# puissance.net
KiCad netlist of a schematic drawn in Altium Designer
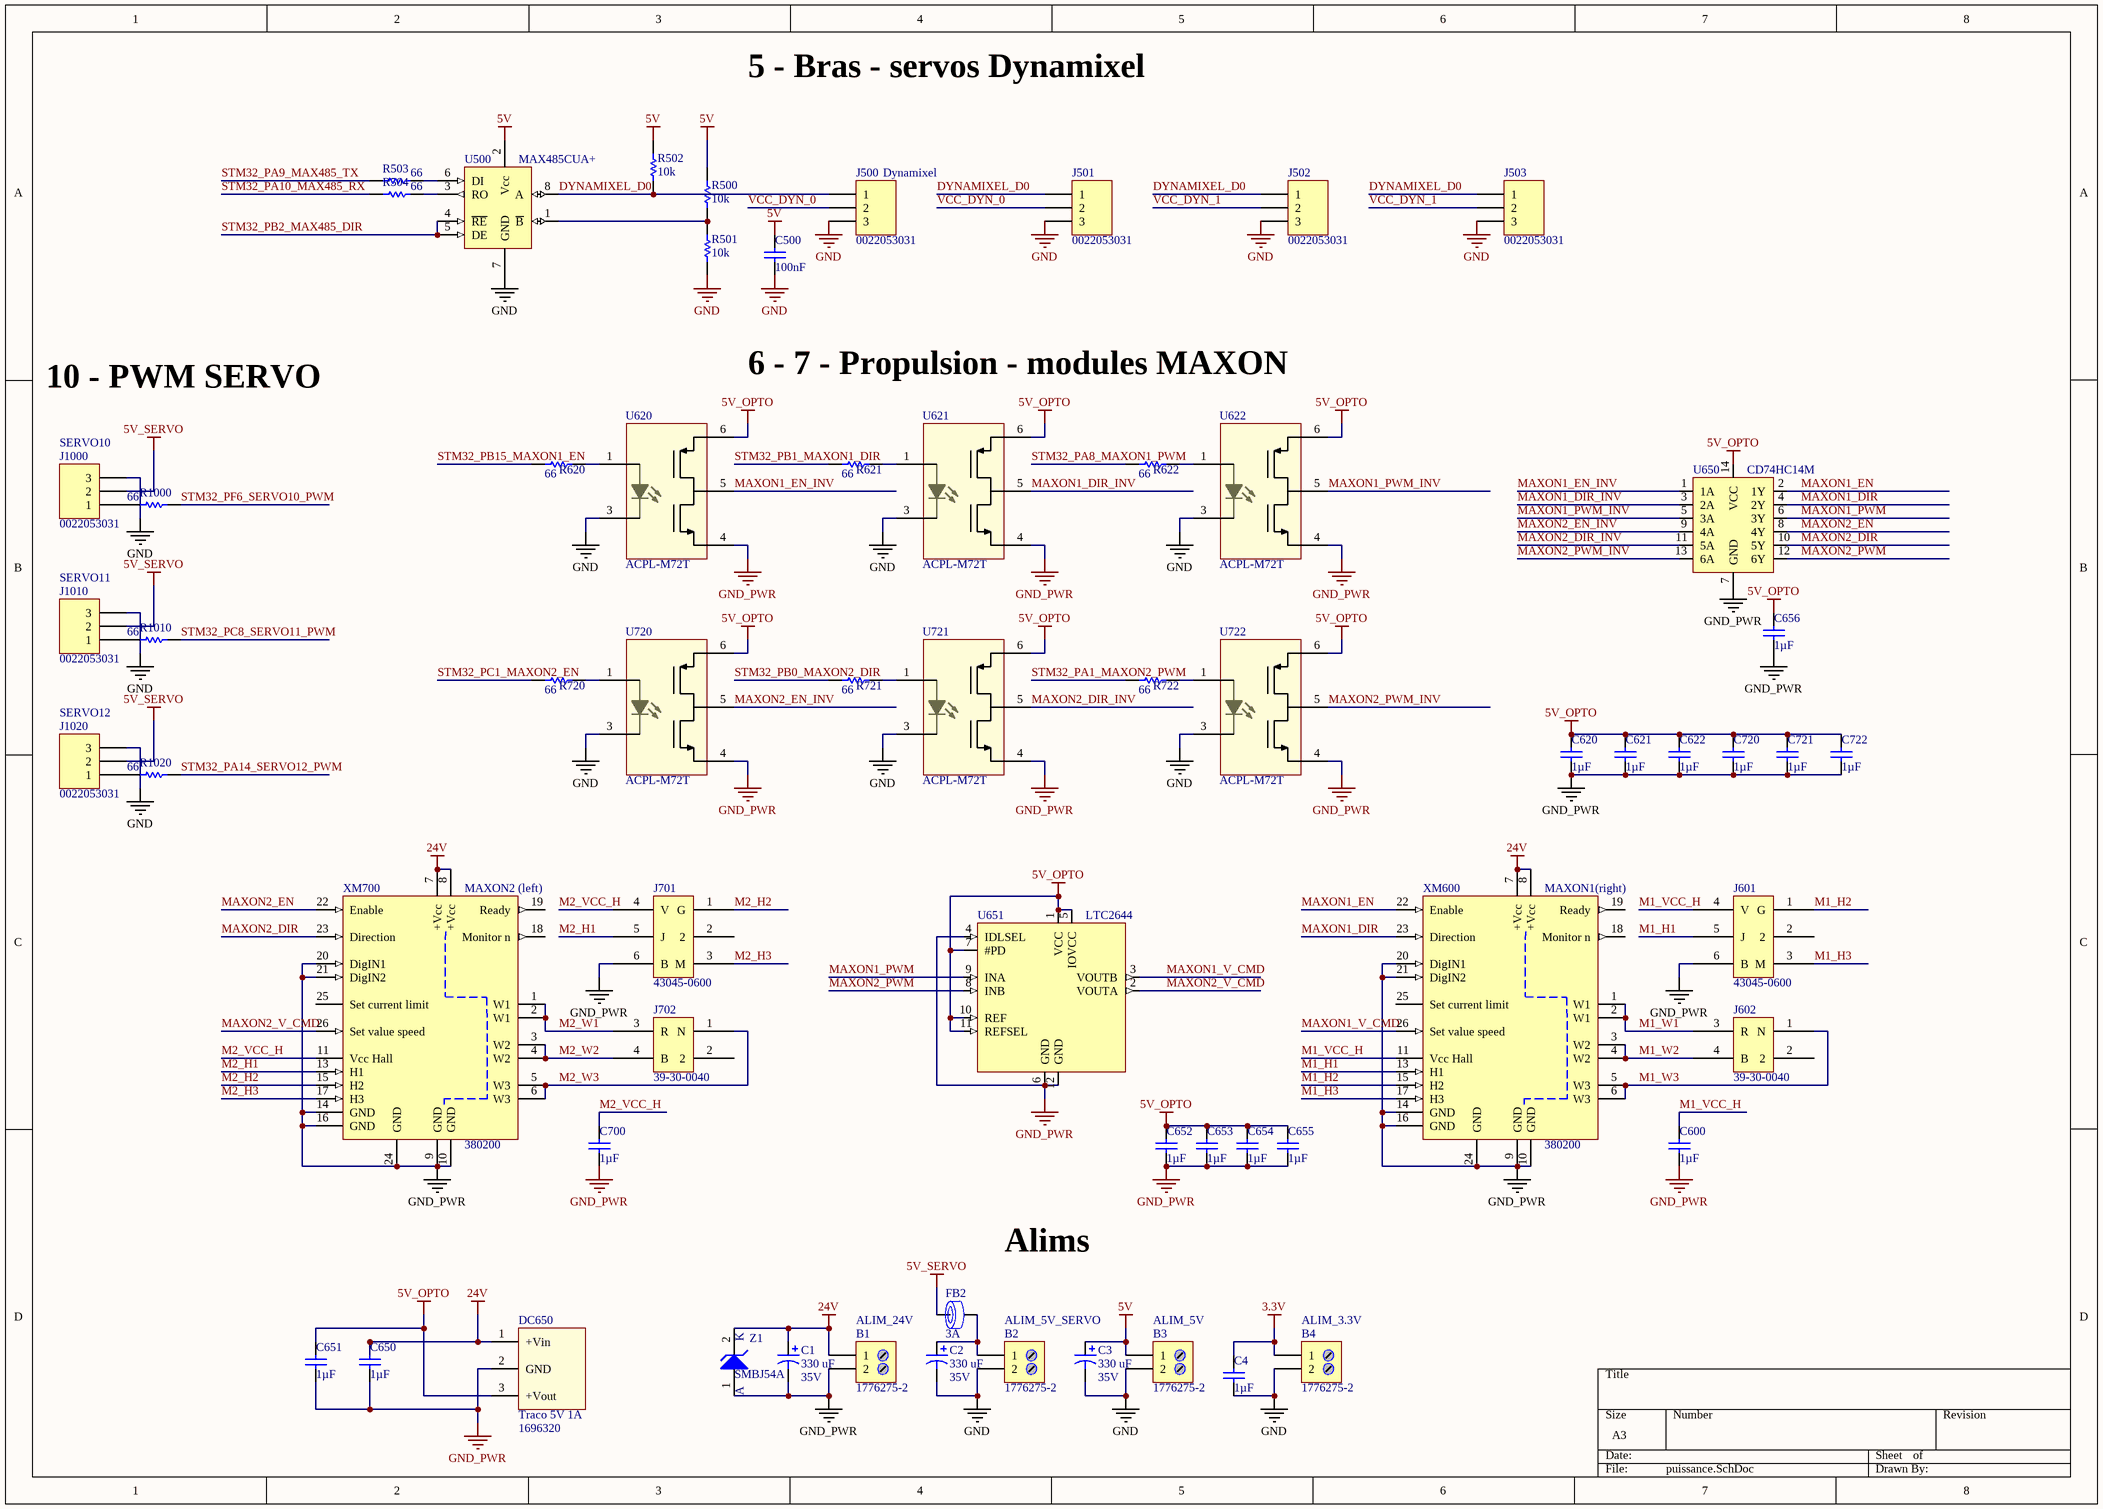
[diagram p0: puissance.SchDoc]

(export (version "E")
  (design (tool "Eeschema 10.0.6"))
  (components
    (comp (ref "B1")
      (value "1776275-2")
      (footprint "BORNIER_2V_3.5MM")
      (description "TERM BLOCK 2POS SIDE ENT 3.5MM")
      (fields (field (name "MANUFACTURER") "TE Connectivity AMP Connectors"))
      (libsource (lib "Divers") (part "1776275-2"))
    )
    (comp (ref "B2")
      (value "1776275-2")
      (footprint "BORNIER_2V_3.5MM")
      (description "TERM BLOCK 2POS SIDE ENT 3.5MM")
      (fields (field (name "MANUFACTURER") "TE Connectivity AMP Connectors"))
      (libsource (lib "Divers") (part "1776275-2"))
    )
    (comp (ref "B3")
      (value "1776275-2")
      (footprint "BORNIER_2V_3.5MM")
      (description "TERM BLOCK 2POS SIDE ENT 3.5MM")
      (fields (field (name "MANUFACTURER") "TE Connectivity AMP Connectors"))
      (libsource (lib "Divers") (part "1776275-2"))
    )
    (comp (ref "B4")
      (value "1776275-2")
      (footprint "BORNIER_2V_3.5MM")
      (description "TERM BLOCK 2POS SIDE ENT 3.5MM")
      (fields (field (name "MANUFACTURER") "TE Connectivity AMP Connectors"))
      (libsource (lib "Divers") (part "1776275-2"))
    )
    (comp (ref "C1")
      (value "330 uF")
      (footprint "WCAP-ATG8_10x12.5x5x0.6")
      (description "CAP Alu 330 UF 20% 35 V")
      (fields
        (field (name "MANUFACTURER") "Wurth Elektronik")
        (field (name "MANUFACTURER PART NUMBER") "860010575012")
        (field (name "RATEDVOLTAGE") "35V")
      )
      (libsource (lib "Condensateur") (part "WCAP-ATG8, 860010575012"))
    )
    (comp (ref "C2")
      (value "330 uF")
      (footprint "WCAP-ATG8_10x12.5x5x0.6")
      (description "CAP Alu 330 UF 20% 35 V")
      (fields
        (field (name "MANUFACTURER") "Wurth Elektronik")
        (field (name "MANUFACTURER PART NUMBER") "860010575012")
        (field (name "RATEDVOLTAGE") "35V")
      )
      (libsource (lib "Condensateur") (part "WCAP-ATG8, 860010575012"))
    )
    (comp (ref "C3")
      (value "330 uF")
      (footprint "WCAP-ATG8_10x12.5x5x0.6")
      (description "CAP Alu 330 UF 20% 35 V")
      (fields
        (field (name "MANUFACTURER") "Wurth Elektronik")
        (field (name "MANUFACTURER PART NUMBER") "860010575012")
        (field (name "RATEDVOLTAGE") "35V")
      )
      (libsource (lib "Condensateur") (part "WCAP-ATG8, 860010575012"))
    )
    (comp (ref "C4")
      (value "1µF")
      (footprint "C0805_N")
      (description "Capacitor")
      (fields (field (name "PUBLISHER") "Altium Limited"))
      (libsource (lib "_ROBOT") (part "Condensateur"))
    )
    (comp (ref "C500")
      (value "100nF")
      (footprint "C0805_N")
      (description "Capacitor")
      (fields (field (name "PUBLISHER") "Altium Limited"))
      (libsource (lib "_ROBOT") (part "Condensateur"))
    )
    (comp (ref "C600")
      (value "1µF")
      (footprint "C0805_N")
      (description "Capacitor")
      (fields (field (name "PUBLISHER") "Altium Limited"))
      (libsource (lib "_ROBOT") (part "Condensateur"))
    )
    (comp (ref "C620")
      (value "1µF")
      (footprint "C0805_N")
      (description "Capacitor")
      (fields (field (name "PUBLISHER") "Altium Limited"))
      (libsource (lib "_ROBOT") (part "Condensateur"))
    )
    (comp (ref "C621")
      (value "1µF")
      (footprint "C0805_N")
      (description "Capacitor")
      (fields (field (name "PUBLISHER") "Altium Limited"))
      (libsource (lib "_ROBOT") (part "Condensateur"))
    )
    (comp (ref "C622")
      (value "1µF")
      (footprint "C0805_N")
      (description "Capacitor")
      (fields (field (name "PUBLISHER") "Altium Limited"))
      (libsource (lib "_ROBOT") (part "Condensateur"))
    )
    (comp (ref "C650")
      (value "1µF")
      (footprint "C0805_N")
      (description "Capacitor")
      (fields (field (name "PUBLISHER") "Altium Limited"))
      (libsource (lib "_ROBOT") (part "Condensateur"))
    )
    (comp (ref "C651")
      (value "1µF")
      (footprint "C0805_N")
      (description "Capacitor")
      (fields (field (name "PUBLISHER") "Altium Limited"))
      (libsource (lib "_ROBOT") (part "Condensateur"))
    )
    (comp (ref "C652")
      (value "1µF")
      (footprint "C0805_N")
      (description "Capacitor")
      (fields (field (name "PUBLISHER") "Altium Limited"))
      (libsource (lib "_ROBOT") (part "Condensateur"))
    )
    (comp (ref "C653")
      (value "1µF")
      (footprint "C0805_N")
      (description "Capacitor")
      (fields (field (name "PUBLISHER") "Altium Limited"))
      (libsource (lib "_ROBOT") (part "Condensateur"))
    )
    (comp (ref "C654")
      (value "1µF")
      (footprint "C0805_N")
      (description "Capacitor")
      (fields (field (name "PUBLISHER") "Altium Limited"))
      (libsource (lib "_ROBOT") (part "Condensateur"))
    )
    (comp (ref "C655")
      (value "1µF")
      (footprint "C0805_N")
      (description "Capacitor")
      (fields (field (name "PUBLISHER") "Altium Limited"))
      (libsource (lib "_ROBOT") (part "Condensateur"))
    )
    (comp (ref "C656")
      (value "1µF")
      (footprint "C0805_N")
      (description "Capacitor")
      (fields (field (name "PUBLISHER") "Altium Limited"))
      (libsource (lib "_ROBOT") (part "Condensateur"))
    )
    (comp (ref "C700")
      (value "1µF")
      (footprint "C0805_N")
      (description "Capacitor")
      (fields (field (name "PUBLISHER") "Altium Limited"))
      (libsource (lib "_ROBOT") (part "Condensateur"))
    )
    (comp (ref "C720")
      (value "1µF")
      (footprint "C0805_N")
      (description "Capacitor")
      (fields (field (name "PUBLISHER") "Altium Limited"))
      (libsource (lib "_ROBOT") (part "Condensateur"))
    )
    (comp (ref "C721")
      (value "1µF")
      (footprint "C0805_N")
      (description "Capacitor")
      (fields (field (name "PUBLISHER") "Altium Limited"))
      (libsource (lib "_ROBOT") (part "Condensateur"))
    )
    (comp (ref "C722")
      (value "1µF")
      (footprint "C0805_N")
      (description "Capacitor")
      (fields (field (name "PUBLISHER") "Altium Limited"))
      (libsource (lib "_ROBOT") (part "Condensateur"))
    )
    (comp (ref "DC650")
      (value "Traco 5V 1A")
      (footprint "TSR1")
      (description "Traco 12.0V 12W 1A")
      (fields
        (field (name "MANUFACTURER") "TRACOPOWER")
        (field (name "MANUFACTURER PART NUMBER") "TSR1-2450")
        (field (name "SUPPLIER PART NUMBER 1") "1696320")
      )
      (libsource (lib "Alimentation") (part "TSR1-24120"))
    )
    (comp (ref "FB2")
      (value "742792023")
      (footprint "WE-CBF_0805_High Current")
      (description "Ferrite Bead 120ohm 0805 max3.0A")
      (fields (field (name "MANUFACTURER") "Wurth Elektronik") (field (name "RATEDCURRENT") "3A"))
      (libsource (lib "Inductance") (part "WE-CBF, 742792023"))
    )
    (comp (ref "J500")
      (value "0022053031")
      (footprint "HDR1X3")
      (description "CONN HEADER 3POS .100 R/A TIN")
      (fields (field (name "MANUFACTURER") "Molex, LLC"))
      (libsource (lib "Divers") (part "0022053031"))
    )
    (comp (ref "J501")
      (value "0022053031")
      (footprint "HDR1X3")
      (description "CONN HEADER 3POS .100 R/A TIN")
      (fields (field (name "MANUFACTURER") "Molex, LLC"))
      (libsource (lib "Divers") (part "0022053031"))
    )
    (comp (ref "J502")
      (value "0022053031")
      (footprint "HDR1X3")
      (description "CONN HEADER 3POS .100 R/A TIN")
      (fields (field (name "MANUFACTURER") "Molex, LLC"))
      (libsource (lib "Divers") (part "0022053031"))
    )
    (comp (ref "J503")
      (value "0022053031")
      (footprint "HDR1X3")
      (description "CONN HEADER 3POS .100 R/A TIN")
      (fields (field (name "MANUFACTURER") "Molex, LLC"))
      (libsource (lib "Divers") (part "0022053031"))
    )
    (comp (ref "J601")
      (value "43045-0600")
      (footprint "Molex:43045-0600")
      (description "CONN HEADER 6POS 3MM RT ANG TIN")
      (fields (field (name "MANUFACTURER") "MOLEX"))
      (libsource (lib "Connecteurs") (part "43045-0600"))
    )
    (comp (ref "J602")
      (value "39-30-0040")
      (footprint "Molex:39-30-0040")
      (description "MOLEX  39-30-0040 4.2 mm, 4 Contact(s)")
      (fields (field (name "MANUFACTURER") "MOLEX"))
      (libsource (lib "Connecteurs") (part "39-30-0040"))
    )
    (comp (ref "J701")
      (value "43045-0600")
      (footprint "Molex:43045-0600")
      (description "CONN HEADER 6POS 3MM RT ANG TIN")
      (fields (field (name "MANUFACTURER") "MOLEX"))
      (libsource (lib "Connecteurs") (part "43045-0600"))
    )
    (comp (ref "J702")
      (value "39-30-0040")
      (footprint "Molex:39-30-0040")
      (description "MOLEX  39-30-0040 4.2 mm, 4 Contact(s)")
      (fields (field (name "MANUFACTURER") "MOLEX"))
      (libsource (lib "Connecteurs") (part "39-30-0040"))
    )
    (comp (ref "J1000")
      (value "0022053031")
      (footprint "HDR1X3")
      (description "CONN HEADER 3POS .100 R/A TIN")
      (fields (field (name "MANUFACTURER") "Molex, LLC"))
      (libsource (lib "") (part "0022053031_1"))
    )
    (comp (ref "J1010")
      (value "0022053031")
      (footprint "HDR1X3")
      (description "CONN HEADER 3POS .100 R/A TIN")
      (fields (field (name "MANUFACTURER") "Molex, LLC"))
      (libsource (lib "") (part "0022053031_1"))
    )
    (comp (ref "J1020")
      (value "0022053031")
      (footprint "HDR1X3")
      (description "CONN HEADER 3POS .100 R/A TIN")
      (fields (field (name "MANUFACTURER") "Molex, LLC"))
      (libsource (lib "") (part "0022053031_1"))
    )
    (comp (ref "R500")
      (value "10k")
      (footprint "R0805_N")
      (description "Resistor")
      (fields (field (name "PUBLISHER") "Altium Limited"))
      (libsource (lib "_ROBOT") (part "Resistor"))
    )
    (comp (ref "R501")
      (value "10k")
      (footprint "R0805_N")
      (description "Resistor")
      (fields (field (name "PUBLISHER") "Altium Limited"))
      (libsource (lib "_ROBOT") (part "Resistor"))
    )
    (comp (ref "R502")
      (value "10k")
      (footprint "R0805_N")
      (description "Resistor")
      (fields (field (name "PUBLISHER") "Altium Limited"))
      (libsource (lib "_ROBOT") (part "Resistor"))
    )
    (comp (ref "R503")
      (value "66")
      (footprint "R0805_N")
      (description "Resistor")
      (fields (field (name "PUBLISHER") "Altium Limited"))
      (libsource (lib "_ROBOT") (part "Resistor"))
    )
    (comp (ref "R504")
      (value "66")
      (footprint "R0805_N")
      (description "Resistor")
      (fields (field (name "PUBLISHER") "Altium Limited"))
      (libsource (lib "_ROBOT") (part "Resistor"))
    )
    (comp (ref "R620")
      (value "66")
      (footprint "R0805_N")
      (description "Resistor")
      (fields (field (name "PUBLISHER") "Altium Limited"))
      (libsource (lib "_ROBOT") (part "Resistor"))
    )
    (comp (ref "R621")
      (value "66")
      (footprint "R0805_N")
      (description "Resistor")
      (fields (field (name "PUBLISHER") "Altium Limited"))
      (libsource (lib "_ROBOT") (part "Resistor"))
    )
    (comp (ref "R622")
      (value "66")
      (footprint "R0805_N")
      (description "Resistor")
      (fields (field (name "PUBLISHER") "Altium Limited"))
      (libsource (lib "_ROBOT") (part "Resistor"))
    )
    (comp (ref "R720")
      (value "66")
      (footprint "R0805_N")
      (description "Resistor")
      (fields (field (name "PUBLISHER") "Altium Limited"))
      (libsource (lib "_ROBOT") (part "Resistor"))
    )
    (comp (ref "R721")
      (value "66")
      (footprint "R0805_N")
      (description "Resistor")
      (fields (field (name "PUBLISHER") "Altium Limited"))
      (libsource (lib "_ROBOT") (part "Resistor"))
    )
    (comp (ref "R722")
      (value "66")
      (footprint "R0805_N")
      (description "Resistor")
      (fields (field (name "PUBLISHER") "Altium Limited"))
      (libsource (lib "_ROBOT") (part "Resistor"))
    )
    (comp (ref "R1000")
      (value "66")
      (footprint "R0805_N")
      (description "Resistor")
      (fields (field (name "PUBLISHER") "Altium Limited"))
      (libsource (lib "_ROBOT") (part "Resistor"))
    )
    (comp (ref "R1010")
      (value "66")
      (footprint "R0805_N")
      (description "Resistor")
      (fields (field (name "PUBLISHER") "Altium Limited"))
      (libsource (lib "_ROBOT") (part "Resistor"))
    )
    (comp (ref "R1020")
      (value "66")
      (footprint "R0805_N")
      (description "Resistor")
      (fields (field (name "PUBLISHER") "Altium Limited"))
      (libsource (lib "_ROBOT") (part "Resistor"))
    )
    (comp (ref "U500")
      (value "MAX485CUA+")
      (footprint "Serial_goldo:MMAX-8")
      (description "IC TXRX RS485/RS422 8-UMAX")
      (fields (field (name "MANUFACTURER") "Maxim Integrated"))
      (libsource (lib "Serial") (part "MAX485CUA+"))
    )
    (comp (ref "U620")
      (value "ACPL-M72T")
      (footprint "ACPL-M72T")
      (description "Optocoupleur")
      (fields (field (name "MANUFACTURER") "AVAGO TECHNOLOGIES"))
      (libsource (lib "Optoélectronique") (part "ACPL-M72T"))
    )
    (comp (ref "U621")
      (value "ACPL-M72T")
      (footprint "ACPL-M72T")
      (description "Optocoupleur")
      (fields (field (name "MANUFACTURER") "AVAGO TECHNOLOGIES"))
      (libsource (lib "Optoélectronique") (part "ACPL-M72T"))
    )
    (comp (ref "U622")
      (value "ACPL-M72T")
      (footprint "ACPL-M72T")
      (description "Optocoupleur")
      (fields (field (name "MANUFACTURER") "AVAGO TECHNOLOGIES"))
      (libsource (lib "Optoélectronique") (part "ACPL-M72T"))
    )
    (comp (ref "U650")
      (value "CD74HC14M")
      (footprint "SOIC127P600X175-14N")
      (description "IC HEX INV SCHMITT TRIG 14-SOIC")
      (fields (field (name "MANUFACTURER") "Texas Instruments"))
      (libsource (lib "Logique") (part "CD74HC14M"))
    )
    (comp (ref "U651")
      (value "LTC2644")
      (footprint "MSOP-12_LTC2644")
      (libsource (lib "CI") (part "LTC2644"))
    )
    (comp (ref "U720")
      (value "ACPL-M72T")
      (footprint "ACPL-M72T")
      (description "Optocoupleur")
      (fields (field (name "MANUFACTURER") "AVAGO TECHNOLOGIES"))
      (libsource (lib "Optoélectronique") (part "ACPL-M72T"))
    )
    (comp (ref "U721")
      (value "ACPL-M72T")
      (footprint "ACPL-M72T")
      (description "Optocoupleur")
      (fields (field (name "MANUFACTURER") "AVAGO TECHNOLOGIES"))
      (libsource (lib "Optoélectronique") (part "ACPL-M72T"))
    )
    (comp (ref "U722")
      (value "ACPL-M72T")
      (footprint "ACPL-M72T")
      (description "Optocoupleur")
      (fields (field (name "MANUFACTURER") "AVAGO TECHNOLOGIES"))
      (libsource (lib "Optoélectronique") (part "ACPL-M72T"))
    )
    (comp (ref "XM600")
      (value "380200")
      (footprint "380200")
      (description "DEC Module 50/5, amplificateur EC 1 Q 50 V / 5 A, régulation de vitesse, module OEM")
      (fields (field (name "MANUFACTURER") "Maxon Motor"))
      (libsource (lib "Divers") (part "380200"))
    )
    (comp (ref "XM700")
      (value "380200")
      (footprint "380200")
      (description "DEC Module 50/5, amplificateur EC 1 Q 50 V / 5 A, régulation de vitesse, module OEM")
      (fields (field (name "MANUFACTURER") "Maxon Motor"))
      (libsource (lib "Divers") (part "380200"))
    )
    (comp (ref "Z1")
      (value "SMBJ54A")
      (footprint "SMA Diode (DO-214AA)")
      (description "DIODE TVS (Transil unidirectionelle)")
      (fields (field (name "MANUFACTURER") "ON Semiconductor"))
      (libsource (lib "Redressement_goldo") (part "SMBJ54A"))
    )
  )
  (nets
    (net (code "1") (name "/DYNAMIXEL_D0") (class "Default")
      (node (ref "J500") (pin "1") (pinfunction "1_1") (pintype "passive"))
      (node (ref "J501") (pin "1") (pinfunction "1_1") (pintype "passive"))
      (node (ref "J502") (pin "1") (pinfunction "1_1") (pintype "passive"))
      (node (ref "J503") (pin "1") (pinfunction "1_1") (pintype "passive"))
      (node (ref "R502") (pin "1") (pinfunction "1_1") (pintype "passive"))
      (node (ref "U500") (pin "8") (pinfunction "A_8") (pintype "bidirectional"))
    )
    (net (code "2") (name "/M1_H1") (class "Default")
      (node (ref "J601") (pin "5") (pinfunction "J_5") (pintype "passive"))
      (node (ref "XM600") (pin "13") (pinfunction "H1_13") (pintype "input"))
    )
    (net (code "3") (name "/M1_H2") (class "Default")
      (node (ref "J601") (pin "1") (pinfunction "G_1") (pintype "passive"))
      (node (ref "XM600") (pin "15") (pinfunction "H2_15") (pintype "input"))
    )
    (net (code "4") (name "/M1_H3") (class "Default")
      (node (ref "J601") (pin "3") (pinfunction "M_3") (pintype "passive"))
      (node (ref "XM600") (pin "17") (pinfunction "H3_17") (pintype "input"))
    )
    (net (code "5") (name "/M1_VCC_H") (class "Default")
      (node (ref "C600") (pin "2") (pinfunction "2_2") (pintype "passive"))
      (node (ref "J601") (pin "4") (pinfunction "V_4") (pintype "passive"))
      (node (ref "XM600") (pin "11") (pinfunction "Vcc_Hall_11") (pintype "power_in"))
    )
    (net (code "6") (name "/M1_W1") (class "Default")
      (node (ref "J602") (pin "3") (pinfunction "R_3") (pintype "passive"))
      (node (ref "XM600") (pin "1") (pinfunction "W1_1") (pintype "passive"))
      (node (ref "XM600") (pin "2") (pinfunction "W1_2") (pintype "passive"))
    )
    (net (code "7") (name "/M1_W2") (class "Default")
      (node (ref "J602") (pin "4") (pinfunction "B_4") (pintype "passive"))
      (node (ref "XM600") (pin "3") (pinfunction "W2_3") (pintype "passive"))
      (node (ref "XM600") (pin "4") (pinfunction "W2_4") (pintype "passive"))
    )
    (net (code "8") (name "/M1_W3") (class "Default")
      (node (ref "J602") (pin "1") (pinfunction "N_1") (pintype "passive"))
      (node (ref "XM600") (pin "5") (pinfunction "W3_5") (pintype "passive"))
      (node (ref "XM600") (pin "6") (pinfunction "W3_6") (pintype "passive"))
    )
    (net (code "9") (name "/M2_H1") (class "Default")
      (node (ref "J701") (pin "5") (pinfunction "J_5") (pintype "passive"))
      (node (ref "XM700") (pin "13") (pinfunction "H1_13") (pintype "input"))
    )
    (net (code "10") (name "/M2_H2") (class "Default")
      (node (ref "J701") (pin "1") (pinfunction "G_1") (pintype "passive"))
      (node (ref "XM700") (pin "15") (pinfunction "H2_15") (pintype "input"))
    )
    (net (code "11") (name "/M2_H3") (class "Default")
      (node (ref "J701") (pin "3") (pinfunction "M_3") (pintype "passive"))
      (node (ref "XM700") (pin "17") (pinfunction "H3_17") (pintype "input"))
    )
    (net (code "12") (name "/M2_VCC_H") (class "Default")
      (node (ref "C700") (pin "2") (pinfunction "2_2") (pintype "passive"))
      (node (ref "J701") (pin "4") (pinfunction "V_4") (pintype "passive"))
      (node (ref "XM700") (pin "11") (pinfunction "Vcc_Hall_11") (pintype "power_in"))
    )
    (net (code "13") (name "/M2_W1") (class "Default")
      (node (ref "J702") (pin "3") (pinfunction "R_3") (pintype "passive"))
      (node (ref "XM700") (pin "1") (pinfunction "W1_1") (pintype "passive"))
      (node (ref "XM700") (pin "2") (pinfunction "W1_2") (pintype "passive"))
    )
    (net (code "14") (name "/M2_W2") (class "Default")
      (node (ref "J702") (pin "4") (pinfunction "B_4") (pintype "passive"))
      (node (ref "XM700") (pin "3") (pinfunction "W2_3") (pintype "passive"))
      (node (ref "XM700") (pin "4") (pinfunction "W2_4") (pintype "passive"))
    )
    (net (code "15") (name "/M2_W3") (class "Default")
      (node (ref "J702") (pin "1") (pinfunction "N_1") (pintype "passive"))
      (node (ref "XM700") (pin "5") (pinfunction "W3_5") (pintype "passive"))
      (node (ref "XM700") (pin "6") (pinfunction "W3_6") (pintype "passive"))
    )
    (net (code "16") (name "/MAXON1_DIR") (class "Default")
      (node (ref "U650") (pin "4") (pinfunction "2Y_4") (pintype "passive"))
      (node (ref "XM600") (pin "23") (pinfunction "Direction_23") (pintype "input"))
    )
    (net (code "17") (name "/MAXON1_DIR_INV") (class "Default")
      (node (ref "U621") (pin "5") (pinfunction "Vo_5") (pintype "passive"))
      (node (ref "U650") (pin "3") (pinfunction "2A_3") (pintype "passive"))
    )
    (net (code "18") (name "/MAXON1_EN") (class "Default")
      (node (ref "U650") (pin "2") (pinfunction "1Y_2") (pintype "passive"))
      (node (ref "XM600") (pin "22") (pinfunction "Enable_22") (pintype "input"))
    )
    (net (code "19") (name "/MAXON1_EN_INV") (class "Default")
      (node (ref "U620") (pin "5") (pinfunction "Vo_5") (pintype "passive"))
      (node (ref "U650") (pin "1") (pinfunction "1A_1") (pintype "passive"))
    )
    (net (code "20") (name "/MAXON1_PWM") (class "Default")
      (node (ref "U650") (pin "6") (pinfunction "3Y_6") (pintype "passive"))
      (node (ref "U651") (pin "9") (pinfunction "INA_9") (pintype "input"))
    )
    (net (code "21") (name "/MAXON1_PWM_INV") (class "Default")
      (node (ref "U622") (pin "5") (pinfunction "Vo_5") (pintype "passive"))
      (node (ref "U650") (pin "5") (pinfunction "3A_5") (pintype "passive"))
    )
    (net (code "22") (name "/MAXON1_V_CMD") (class "Default")
      (node (ref "U651") (pin "3") (pinfunction "VOUTB_3") (pintype "output"))
      (node (ref "XM600") (pin "26") (pinfunction "Set_value_speed_26") (pintype "input"))
    )
    (net (code "23") (name "/MAXON2_DIR") (class "Default")
      (node (ref "U650") (pin "10") (pinfunction "5Y_10") (pintype "passive"))
      (node (ref "XM700") (pin "23") (pinfunction "Direction_23") (pintype "input"))
    )
    (net (code "24") (name "/MAXON2_DIR_INV") (class "Default")
      (node (ref "U650") (pin "11") (pinfunction "5A_11") (pintype "passive"))
      (node (ref "U721") (pin "5") (pinfunction "Vo_5") (pintype "passive"))
    )
    (net (code "25") (name "/MAXON2_EN") (class "Default")
      (node (ref "U650") (pin "8") (pinfunction "4Y_8") (pintype "passive"))
      (node (ref "XM700") (pin "22") (pinfunction "Enable_22") (pintype "input"))
    )
    (net (code "26") (name "/MAXON2_EN_INV") (class "Default")
      (node (ref "U650") (pin "9") (pinfunction "4A_9") (pintype "passive"))
      (node (ref "U720") (pin "5") (pinfunction "Vo_5") (pintype "passive"))
    )
    (net (code "27") (name "/MAXON2_PWM") (class "Default")
      (node (ref "U650") (pin "12") (pinfunction "6Y_12") (pintype "passive"))
      (node (ref "U651") (pin "8") (pinfunction "INB_8") (pintype "input"))
    )
    (net (code "28") (name "/MAXON2_PWM_INV") (class "Default")
      (node (ref "U650") (pin "13") (pinfunction "6A_13") (pintype "passive"))
      (node (ref "U722") (pin "5") (pinfunction "Vo_5") (pintype "passive"))
    )
    (net (code "29") (name "/MAXON2_V_CMD") (class "Default")
      (node (ref "U651") (pin "2") (pinfunction "VOUTA_2") (pintype "output"))
      (node (ref "XM700") (pin "26") (pinfunction "Set_value_speed_26") (pintype "input"))
    )
    (net (code "30") (name "/STM32_PA1_MAXON2_PWM") (class "Default")
      (node (ref "R722") (pin "1") (pinfunction "1_1") (pintype "passive"))
    )
    (net (code "31") (name "/STM32_PA8_MAXON1_PWM") (class "Default")
      (node (ref "R622") (pin "1") (pinfunction "1_1") (pintype "passive"))
    )
    (net (code "32") (name "/STM32_PA9_MAX485_TX") (class "Default")
      (node (ref "R503") (pin "2") (pinfunction "2_2") (pintype "passive"))
    )
    (net (code "33") (name "/STM32_PA10_MAX485_RX") (class "Default")
      (node (ref "R504") (pin "2") (pinfunction "2_2") (pintype "passive"))
    )
    (net (code "34") (name "/STM32_PA14_SERVO12_PWM") (class "Default")
      (node (ref "R1020") (pin "1") (pinfunction "1_1") (pintype "passive"))
    )
    (net (code "35") (name "/STM32_PB0_MAXON2_DIR") (class "Default")
      (node (ref "R721") (pin "1") (pinfunction "1_1") (pintype "passive"))
    )
    (net (code "36") (name "/STM32_PB1_MAXON1_DIR") (class "Default")
      (node (ref "R621") (pin "1") (pinfunction "1_1") (pintype "passive"))
    )
    (net (code "37") (name "/STM32_PB2_MAX485_DIR") (class "Default")
      (node (ref "U500") (pin "4") (pinfunction "~{RE}_4") (pintype "input"))
      (node (ref "U500") (pin "5") (pinfunction "DE_5") (pintype "input"))
    )
    (net (code "38") (name "/STM32_PB15_MAXON1_EN") (class "Default")
      (node (ref "R620") (pin "1") (pinfunction "1_1") (pintype "passive"))
    )
    (net (code "39") (name "/STM32_PC1_MAXON2_EN") (class "Default")
      (node (ref "R720") (pin "1") (pinfunction "1_1") (pintype "passive"))
    )
    (net (code "40") (name "/STM32_PC8_SERVO11_PWM") (class "Default")
      (node (ref "R1010") (pin "1") (pinfunction "1_1") (pintype "passive"))
    )
    (net (code "41") (name "/STM32_PF6_SERVO10_PWM") (class "Default")
      (node (ref "R1000") (pin "1") (pinfunction "1_1") (pintype "passive"))
    )
    (net (code "42") (name "/VCC_DYN_0") (class "Default")
      (node (ref "J500") (pin "2") (pinfunction "2_2") (pintype "passive"))
      (node (ref "J501") (pin "2") (pinfunction "2_2") (pintype "passive"))
    )
    (net (code "43") (name "/VCC_DYN_1") (class "Default")
      (node (ref "J502") (pin "2") (pinfunction "2_2") (pintype "passive"))
      (node (ref "J503") (pin "2") (pinfunction "2_2") (pintype "passive"))
    )
    (net (code "44") (name "3.3V") (class "Default")
      (node (ref "B4") (pin "1") (pinfunction "1_1") (pintype "passive"))
      (node (ref "C4") (pin "2") (pinfunction "2_2") (pintype "passive"))
    )
    (net (code "45") (name "5V") (class "Default")
      (node (ref "B3") (pin "1") (pinfunction "1_1") (pintype "passive"))
      (node (ref "C3") (pin "1") (pinfunction "1_1") (pintype "passive"))
      (node (ref "C500") (pin "2") (pinfunction "2_2") (pintype "passive"))
      (node (ref "R500") (pin "2") (pinfunction "2_2") (pintype "passive"))
      (node (ref "R502") (pin "2") (pinfunction "2_2") (pintype "passive"))
      (node (ref "U500") (pin "2") (pinfunction "Vcc_2") (pintype "power_in"))
    )
    (net (code "46") (name "5V_OPTO") (class "Default")
      (node (ref "C620") (pin "2") (pinfunction "2_2") (pintype "passive"))
      (node (ref "C621") (pin "2") (pinfunction "2_2") (pintype "passive"))
      (node (ref "C622") (pin "2") (pinfunction "2_2") (pintype "passive"))
      (node (ref "C651") (pin "2") (pinfunction "2_2") (pintype "passive"))
      (node (ref "C652") (pin "2") (pinfunction "2_2") (pintype "passive"))
      (node (ref "C653") (pin "2") (pinfunction "2_2") (pintype "passive"))
      (node (ref "C654") (pin "2") (pinfunction "2_2") (pintype "passive"))
      (node (ref "C655") (pin "2") (pinfunction "2_2") (pintype "passive"))
      (node (ref "C656") (pin "2") (pinfunction "2_2") (pintype "passive"))
      (node (ref "C720") (pin "2") (pinfunction "2_2") (pintype "passive"))
      (node (ref "C721") (pin "2") (pinfunction "2_2") (pintype "passive"))
      (node (ref "C722") (pin "2") (pinfunction "2_2") (pintype "passive"))
      (node (ref "DC650") (pin "3") (pinfunction "+Vout_3") (pintype "power_in"))
      (node (ref "U620") (pin "6") (pinfunction "VDD_6") (pintype "passive"))
      (node (ref "U621") (pin "6") (pinfunction "VDD_6") (pintype "passive"))
      (node (ref "U622") (pin "6") (pinfunction "VDD_6") (pintype "passive"))
      (node (ref "U650") (pin "14") (pinfunction "VCC_14") (pintype "passive"))
      (node (ref "U651") (pin "1") (pinfunction "VCC_1") (pintype "power_in"))
      (node (ref "U651") (pin "10") (pinfunction "REF_10") (pintype "input"))
      (node (ref "U651") (pin "11") (pinfunction "REFSEL_11") (pintype "input"))
      (node (ref "U651") (pin "5") (pinfunction "IOVCC_5") (pintype "power_in"))
      (node (ref "U651") (pin "7") (pinfunction "#PD_7") (pintype "passive"))
      (node (ref "U720") (pin "6") (pinfunction "VDD_6") (pintype "passive"))
      (node (ref "U721") (pin "6") (pinfunction "VDD_6") (pintype "passive"))
      (node (ref "U722") (pin "6") (pinfunction "VDD_6") (pintype "passive"))
    )
    (net (code "47") (name "5V_SERVO") (class "Default")
      (node (ref "FB2") (pin "1") (pinfunction "1_1") (pintype "passive"))
      (node (ref "J1000") (pin "2") (pinfunction "2_2") (pintype "passive"))
      (node (ref "J1010") (pin "2") (pinfunction "2_2") (pintype "passive"))
      (node (ref "J1020") (pin "2") (pinfunction "2_2") (pintype "passive"))
    )
    (net (code "48") (name "24V") (class "Default")
      (node (ref "B1") (pin "1") (pinfunction "1_1") (pintype "passive"))
      (node (ref "C1") (pin "1") (pinfunction "1_1") (pintype "passive"))
      (node (ref "C650") (pin "2") (pinfunction "2_2") (pintype "passive"))
      (node (ref "DC650") (pin "1") (pinfunction "+Vin_1") (pintype "power_in"))
      (node (ref "XM600") (pin "7") (pinfunction "+Vcc_7") (pintype "power_in"))
      (node (ref "XM600") (pin "8") (pinfunction "+Vcc_8") (pintype "power_in"))
      (node (ref "XM700") (pin "7") (pinfunction "+Vcc_7") (pintype "power_in"))
      (node (ref "XM700") (pin "8") (pinfunction "+Vcc_8") (pintype "power_in"))
      (node (ref "Z1") (pin "2") (pintype "passive"))
    )
    (net (code "49") (name "GND") (class "Default")
      (node (ref "B2") (pin "2") (pinfunction "2_2") (pintype "passive"))
      (node (ref "B3") (pin "2") (pinfunction "2_2") (pintype "passive"))
      (node (ref "B4") (pin "2") (pinfunction "2_2") (pintype "passive"))
      (node (ref "C2") (pin "2") (pinfunction "2_2") (pintype "passive"))
      (node (ref "C3") (pin "2") (pinfunction "2_2") (pintype "passive"))
      (node (ref "C4") (pin "1") (pinfunction "1_1") (pintype "passive"))
      (node (ref "C500") (pin "1") (pinfunction "1_1") (pintype "passive"))
      (node (ref "J1000") (pin "3") (pinfunction "3_3") (pintype "passive"))
      (node (ref "J1010") (pin "3") (pinfunction "3_3") (pintype "passive"))
      (node (ref "J1020") (pin "3") (pinfunction "3_3") (pintype "passive"))
      (node (ref "J500") (pin "3") (pinfunction "3_3") (pintype "passive"))
      (node (ref "J501") (pin "3") (pinfunction "3_3") (pintype "passive"))
      (node (ref "J502") (pin "3") (pinfunction "3_3") (pintype "passive"))
      (node (ref "J503") (pin "3") (pinfunction "3_3") (pintype "passive"))
      (node (ref "R501") (pin "1") (pinfunction "1_1") (pintype "passive"))
      (node (ref "U500") (pin "7") (pinfunction "GND_7") (pintype "power_in"))
      (node (ref "U620") (pin "3") (pinfunction "Cathode_3") (pintype "passive"))
      (node (ref "U621") (pin "3") (pinfunction "Cathode_3") (pintype "passive"))
      (node (ref "U622") (pin "3") (pinfunction "Cathode_3") (pintype "passive"))
      (node (ref "U720") (pin "3") (pinfunction "Cathode_3") (pintype "passive"))
      (node (ref "U721") (pin "3") (pinfunction "Cathode_3") (pintype "passive"))
      (node (ref "U722") (pin "3") (pinfunction "Cathode_3") (pintype "passive"))
    )
    (net (code "50") (name "GND_PWR") (class "Default")
      (node (ref "B1") (pin "2") (pinfunction "2_2") (pintype "passive"))
      (node (ref "C1") (pin "2") (pinfunction "2_2") (pintype "passive"))
      (node (ref "C600") (pin "1") (pinfunction "1_1") (pintype "passive"))
      (node (ref "C620") (pin "1") (pinfunction "1_1") (pintype "passive"))
      (node (ref "C621") (pin "1") (pinfunction "1_1") (pintype "passive"))
      (node (ref "C622") (pin "1") (pinfunction "1_1") (pintype "passive"))
      (node (ref "C650") (pin "1") (pinfunction "1_1") (pintype "passive"))
      (node (ref "C651") (pin "1") (pinfunction "1_1") (pintype "passive"))
      (node (ref "C652") (pin "1") (pinfunction "1_1") (pintype "passive"))
      (node (ref "C653") (pin "1") (pinfunction "1_1") (pintype "passive"))
      (node (ref "C654") (pin "1") (pinfunction "1_1") (pintype "passive"))
      (node (ref "C655") (pin "1") (pinfunction "1_1") (pintype "passive"))
      (node (ref "C656") (pin "1") (pinfunction "1_1") (pintype "passive"))
      (node (ref "C700") (pin "1") (pinfunction "1_1") (pintype "passive"))
      (node (ref "C720") (pin "1") (pinfunction "1_1") (pintype "passive"))
      (node (ref "C721") (pin "1") (pinfunction "1_1") (pintype "passive"))
      (node (ref "C722") (pin "1") (pinfunction "1_1") (pintype "passive"))
      (node (ref "DC650") (pin "2") (pinfunction "GND_2") (pintype "power_in"))
      (node (ref "J601") (pin "6") (pinfunction "B_6") (pintype "passive"))
      (node (ref "J701") (pin "6") (pinfunction "B_6") (pintype "passive"))
      (node (ref "U620") (pin "4") (pinfunction "GND_4") (pintype "passive"))
      (node (ref "U621") (pin "4") (pinfunction "GND_4") (pintype "passive"))
      (node (ref "U622") (pin "4") (pinfunction "GND_4") (pintype "passive"))
      (node (ref "U650") (pin "7") (pinfunction "GND_7") (pintype "passive"))
      (node (ref "U651") (pin "12") (pinfunction "GND_12") (pintype "power_in"))
      (node (ref "U651") (pin "4") (pinfunction "IDLSEL_4") (pintype "input"))
      (node (ref "U651") (pin "6") (pinfunction "GND_6") (pintype "power_in"))
      (node (ref "U720") (pin "4") (pinfunction "GND_4") (pintype "passive"))
      (node (ref "U721") (pin "4") (pinfunction "GND_4") (pintype "passive"))
      (node (ref "U722") (pin "4") (pinfunction "GND_4") (pintype "passive"))
      (node (ref "XM600") (pin "10") (pinfunction "GND_10") (pintype "power_in"))
      (node (ref "XM600") (pin "14") (pinfunction "GND_14") (pintype "power_in"))
      (node (ref "XM600") (pin "16") (pinfunction "GND_16") (pintype "power_in"))
      (node (ref "XM600") (pin "20") (pinfunction "DigIN1_20") (pintype "input"))
      (node (ref "XM600") (pin "21") (pinfunction "DigIN2_21") (pintype "input"))
      (node (ref "XM600") (pin "24") (pinfunction "GND_24") (pintype "power_in"))
      (node (ref "XM600") (pin "9") (pinfunction "GND_9") (pintype "power_in"))
      (node (ref "XM700") (pin "10") (pinfunction "GND_10") (pintype "power_in"))
      (node (ref "XM700") (pin "14") (pinfunction "GND_14") (pintype "power_in"))
      (node (ref "XM700") (pin "16") (pinfunction "GND_16") (pintype "power_in"))
      (node (ref "XM700") (pin "20") (pinfunction "DigIN1_20") (pintype "input"))
      (node (ref "XM700") (pin "21") (pinfunction "DigIN2_21") (pintype "input"))
      (node (ref "XM700") (pin "24") (pinfunction "GND_24") (pintype "power_in"))
      (node (ref "XM700") (pin "9") (pinfunction "GND_9") (pintype "power_in"))
      (node (ref "Z1") (pin "1") (pintype "passive"))
    )
    (net (code "51") (name "Net-(B2-Pad1)") (class "Default")
      (node (ref "B2") (pin "1") (pinfunction "1_1") (pintype "passive"))
      (node (ref "C2") (pin "1") (pinfunction "1_1") (pintype "passive"))
      (node (ref "FB2") (pin "2") (pinfunction "2_2") (pintype "passive"))
    )
    (net (code "52") (name "Net-(J1000-Pad1)") (class "Default")
      (node (ref "J1000") (pin "1") (pinfunction "1_1") (pintype "passive"))
      (node (ref "R1000") (pin "2") (pinfunction "2_2") (pintype "passive"))
    )
    (net (code "53") (name "Net-(J1010-Pad1)") (class "Default")
      (node (ref "J1010") (pin "1") (pinfunction "1_1") (pintype "passive"))
      (node (ref "R1010") (pin "2") (pinfunction "2_2") (pintype "passive"))
    )
    (net (code "54") (name "Net-(J1020-Pad1)") (class "Default")
      (node (ref "J1020") (pin "1") (pinfunction "1_1") (pintype "passive"))
      (node (ref "R1020") (pin "2") (pinfunction "2_2") (pintype "passive"))
    )
    (net (code "55") (name "Net-(U500-DI)") (class "Default")
      (node (ref "R503") (pin "1") (pinfunction "1_1") (pintype "passive"))
      (node (ref "U500") (pin "6") (pinfunction "DI_6") (pintype "input"))
    )
    (net (code "56") (name "Net-(U500-RO)") (class "Default")
      (node (ref "R504") (pin "1") (pinfunction "1_1") (pintype "passive"))
      (node (ref "U500") (pin "3") (pinfunction "RO_3") (pintype "output"))
    )
    (net (code "57") (name "Net-(U500-~{B})") (class "Default")
      (node (ref "R500") (pin "1") (pinfunction "1_1") (pintype "passive"))
      (node (ref "R501") (pin "2") (pinfunction "2_2") (pintype "passive"))
      (node (ref "U500") (pin "1") (pinfunction "~{B}_1") (pintype "bidirectional"))
    )
    (net (code "58") (name "Net-(U620-Anode)") (class "Default")
      (node (ref "R620") (pin "2") (pinfunction "2_2") (pintype "passive"))
      (node (ref "U620") (pin "1") (pinfunction "Anode_1") (pintype "passive"))
    )
    (net (code "59") (name "Net-(U621-Anode)") (class "Default")
      (node (ref "R621") (pin "2") (pinfunction "2_2") (pintype "passive"))
      (node (ref "U621") (pin "1") (pinfunction "Anode_1") (pintype "passive"))
    )
    (net (code "60") (name "Net-(U622-Anode)") (class "Default")
      (node (ref "R622") (pin "2") (pinfunction "2_2") (pintype "passive"))
      (node (ref "U622") (pin "1") (pinfunction "Anode_1") (pintype "passive"))
    )
    (net (code "61") (name "Net-(U720-Anode)") (class "Default")
      (node (ref "R720") (pin "2") (pinfunction "2_2") (pintype "passive"))
      (node (ref "U720") (pin "1") (pinfunction "Anode_1") (pintype "passive"))
    )
    (net (code "62") (name "Net-(U721-Anode)") (class "Default")
      (node (ref "R721") (pin "2") (pinfunction "2_2") (pintype "passive"))
      (node (ref "U721") (pin "1") (pinfunction "Anode_1") (pintype "passive"))
    )
    (net (code "63") (name "Net-(U722-Anode)") (class "Default")
      (node (ref "R722") (pin "2") (pinfunction "2_2") (pintype "passive"))
      (node (ref "U722") (pin "1") (pinfunction "Anode_1") (pintype "passive"))
    )
    (net (code "64") (name "unconnected-(J601-Pad2)") (class "Default")
      (node (ref "J601") (pin "2") (pinfunction "2_2") (pintype "passive"))
    )
    (net (code "65") (name "unconnected-(J602-Pad2)") (class "Default")
      (node (ref "J602") (pin "2") (pinfunction "2_2") (pintype "passive"))
    )
    (net (code "66") (name "unconnected-(J701-Pad2)") (class "Default")
      (node (ref "J701") (pin "2") (pinfunction "2_2") (pintype "passive"))
    )
    (net (code "67") (name "unconnected-(J702-Pad2)") (class "Default")
      (node (ref "J702") (pin "2") (pinfunction "2_2") (pintype "passive"))
    )
    (net (code "68") (name "unconnected-(XM600-Monitor_n-Pad18)") (class "Default")
      (node (ref "XM600") (pin "18") (pinfunction "Monitor_n_18") (pintype "output"))
    )
    (net (code "69") (name "unconnected-(XM600-Ready-Pad19)") (class "Default")
      (node (ref "XM600") (pin "19") (pinfunction "Ready_19") (pintype "output"))
    )
    (net (code "70") (name "unconnected-(XM600-Set_current_limit-Pad25)") (class "Default")
      (node (ref "XM600") (pin "25") (pinfunction "Set_current_limit_25") (pintype "passive"))
    )
    (net (code "71") (name "unconnected-(XM600-nc-Pad12)") (class "Default")
      (node (ref "XM600") (pin "12") (pinfunction "nc_12") (pintype "passive"))
    )
    (net (code "72") (name "unconnected-(XM700-Monitor_n-Pad18)") (class "Default")
      (node (ref "XM700") (pin "18") (pinfunction "Monitor_n_18") (pintype "output"))
    )
    (net (code "73") (name "unconnected-(XM700-Ready-Pad19)") (class "Default")
      (node (ref "XM700") (pin "19") (pinfunction "Ready_19") (pintype "output"))
    )
    (net (code "74") (name "unconnected-(XM700-Set_current_limit-Pad25)") (class "Default")
      (node (ref "XM700") (pin "25") (pinfunction "Set_current_limit_25") (pintype "passive"))
    )
    (net (code "75") (name "unconnected-(XM700-nc-Pad12)") (class "Default")
      (node (ref "XM700") (pin "12") (pinfunction "nc_12") (pintype "passive"))
    )
  )
)
